# USB.net
KiCad netlist of a schematic drawn in Altium Designer
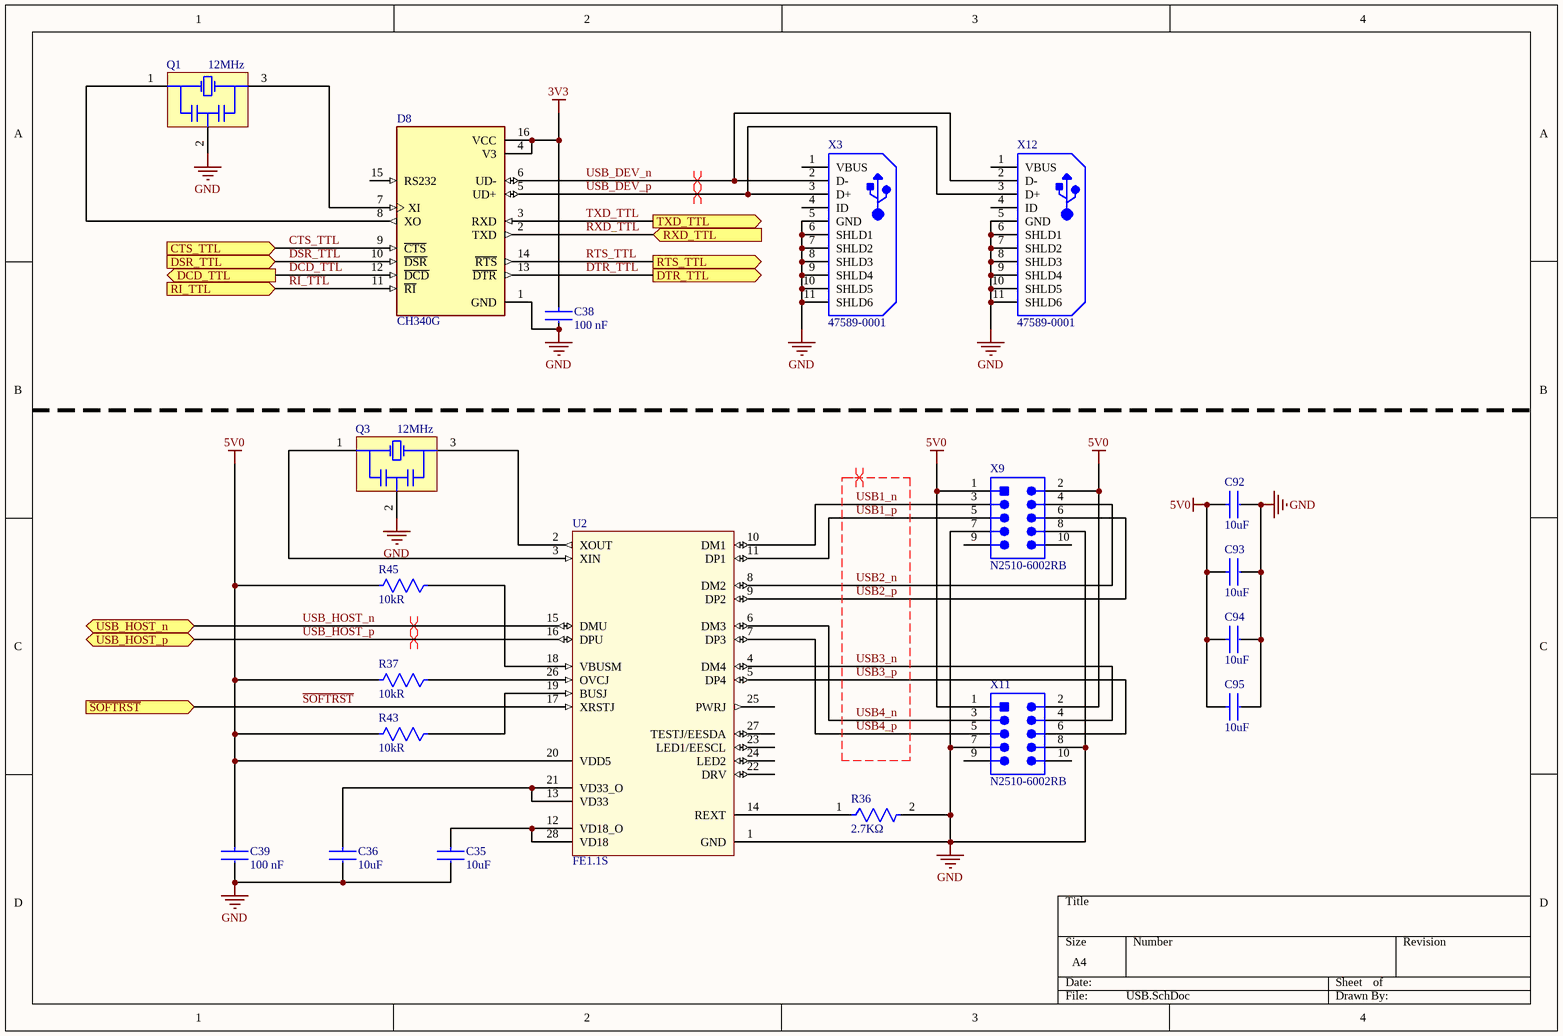
[diagram p0: USB.SchDoc]

(export (version "E")
  (design (tool "Eeschema 10.0.6"))
  (components
    (comp (ref "C35")
      (value "C0805C106K8PACTU")
      (footprint "FP-C0805C-DG-IPC_A")
      (description "CAP CER 10UF 10V X5R 0805")
      (fields (field (name "MANUFACTURER") "KEMET") (field (name "CAPACITANCE") "10uF"))
      (libsource (lib "zxevo") (part "CMP-2007-03243-2"))
    )
    (comp (ref "C36")
      (value "C0805C106K8PACTU")
      (footprint "FP-C0805C-DG-IPC_A")
      (description "CAP CER 10UF 10V X5R 0805")
      (fields (field (name "MANUFACTURER") "KEMET") (field (name "CAPACITANCE") "10uF"))
      (libsource (lib "zxevo") (part "CMP-2007-03243-2"))
    )
    (comp (ref "C38")
      (value "CC0805KRX7R9BB104")
      (footprint "FP-CC0805-0_85-IPC_A")
      (description "CAP CER 0.1UF 50V X7R 0805")
      (fields (field (name "MANUFACTURER") "Yageo") (field (name "CAPACITANCE") "100 nF"))
      (libsource (lib "zxevo") (part "CMP-2100-03606-3"))
    )
    (comp (ref "C39")
      (value "CC0805KRX7R9BB104")
      (footprint "FP-CC0805-0_85-IPC_A")
      (description "CAP CER 0.1UF 50V X7R 0805")
      (fields (field (name "MANUFACTURER") "Yageo") (field (name "CAPACITANCE") "100 nF"))
      (libsource (lib "zxevo") (part "CMP-2100-03606-3"))
    )
    (comp (ref "C92")
      (value "C0805C106K8PACTU")
      (footprint "FP-C0805C-DG-IPC_A")
      (description "CAP CER 10UF 10V X5R 0805")
      (fields (field (name "MANUFACTURER") "KEMET") (field (name "CAPACITANCE") "10uF"))
      (libsource (lib "zxevo") (part "CMP-2007-03243-2"))
    )
    (comp (ref "C93")
      (value "C0805C106K8PACTU")
      (footprint "FP-C0805C-DG-IPC_A")
      (description "CAP CER 10UF 10V X5R 0805")
      (fields (field (name "MANUFACTURER") "KEMET") (field (name "CAPACITANCE") "10uF"))
      (libsource (lib "zxevo") (part "CMP-2007-03243-2"))
    )
    (comp (ref "C94")
      (value "C0805C106K8PACTU")
      (footprint "FP-C0805C-DG-IPC_A")
      (description "CAP CER 10UF 10V X5R 0805")
      (fields (field (name "MANUFACTURER") "KEMET") (field (name "CAPACITANCE") "10uF"))
      (libsource (lib "zxevo") (part "CMP-2007-03243-2"))
    )
    (comp (ref "C95")
      (value "C0805C106K8PACTU")
      (footprint "FP-C0805C-DG-IPC_A")
      (description "CAP CER 10UF 10V X5R 0805")
      (fields (field (name "MANUFACTURER") "KEMET") (field (name "CAPACITANCE") "10uF"))
      (libsource (lib "zxevo") (part "CMP-2007-03243-2"))
    )
    (comp (ref "D8")
      (value "CH340G")
      (footprint "SOIC127P600X180-16N")
      (description "USB Interface Integrated Circuit")
      (libsource (lib "zxevo") (part "CH340G"))
    )
    (comp (ref "Q1")
      (value "CSTCE12M0G55Z-R0")
      (footprint "MURA-CSTCE_G_V")
      (description "Ceramic Resonator, 12 MHz, +/- 0.5%, -40 to 125 degC, 3-Pin SMD, RoHS, Tape and Reel")
      (fields (field (name "FREQUENCY") "12MHz") (field (name "MANUFACTURER") "Murata"))
      (libsource (lib "zxevo") (part "CMP-2000-06123-1"))
    )
    (comp (ref "Q3")
      (value "CSTCE12M0G55Z-R0")
      (footprint "MURA-CSTCE_G_V")
      (description "Ceramic Resonator, 12 MHz, +/- 0.5%, -40 to 125 degC, 3-Pin SMD, RoHS, Tape and Reel")
      (fields (field (name "FREQUENCY") "12MHz") (field (name "MANUFACTURER") "Murata"))
      (libsource (lib "zxevo") (part "CMP-2000-06123-1"))
    )
    (comp (ref "R36")
      (value "AC0805FR-072K7L")
      (footprint "FP-AC0805-IPC_A")
      (description "RES SMD 2.7K OHM 1% 1/8W 0805")
      (fields (field (name "RESISTANCE") "2.7KΩ") (field (name "MANUFACTURER") "Yageo"))
      (libsource (lib "zxevo") (part "CMP-2001-04496-2"))
    )
    (comp (ref "R37")
      (value "CR0805-JW-103ELF")
      (footprint "FP-CR0805-IPC_A")
      (description "Thick Film Chip Resistors 0805 10kΩ 0.125W 5% 200ppm/°C")
      (fields (field (name "RESISTANCE") "10kR") (field (name "MANUFACTURER") "Bourns"))
      (libsource (lib "zxevo") (part "CMP-07231-003873-1"))
    )
    (comp (ref "R43")
      (value "CR0805-JW-103ELF")
      (footprint "FP-CR0805-IPC_A")
      (description "Thick Film Chip Resistors 0805 10kΩ 0.125W 5% 200ppm/°C")
      (fields (field (name "RESISTANCE") "10kR") (field (name "MANUFACTURER") "Bourns"))
      (libsource (lib "zxevo") (part "CMP-07231-003873-1"))
    )
    (comp (ref "R45")
      (value "CR0805-JW-103ELF")
      (footprint "FP-CR0805-IPC_A")
      (description "Thick Film Chip Resistors 0805 10kΩ 0.125W 5% 200ppm/°C")
      (fields (field (name "RESISTANCE") "10kR") (field (name "MANUFACTURER") "Bourns"))
      (libsource (lib "zxevo") (part "CMP-07231-003873-1"))
    )
    (comp (ref "U2")
      (value "FE1.1S")
      (footprint "TSOP64P600X160-28L")
      (description "USB 2.0 HIGH SPEED 4-PORT HUB CONTROLLER")
      (fields (field (name "MANUFACTURER") "Terminus Technology Inc"))
      (libsource (lib "zxevo") (part "FE1.1S"))
    )
    (comp (ref "X3")
      (value "47589-0001")
      (footprint "MOLX-47589-0001_V")
      (description "Right Angle Female Type AB Micro USB Connector, 30 V, 1.8 A, -30 to 85 degC, RoHS, Tape and Reel")
      (fields (field (name "MANUFACTURER") "Molex"))
      (libsource (lib "zxevo") (part "CMP-2000-05610-1"))
    )
    (comp (ref "X9")
      (value "N2510-6002RB")
      (footprint "3M-N2510-6002-10_V")
      (fields (field (name "PARTNUMBER") "N2510") (field (name "MANUFACTURER") "3M"))
      (libsource (lib "zxevo") (part "CMP-2000-06794-1"))
    )
    (comp (ref "X11")
      (value "N2510-6002RB")
      (footprint "3M-N2510-6002-10_V")
      (fields (field (name "PARTNUMBER") "N2510") (field (name "MANUFACTURER") "3M"))
      (libsource (lib "zxevo") (part "CMP-2000-06794-1"))
    )
    (comp (ref "X12")
      (value "47589-0001")
      (footprint "MOLX-47589-0001_V")
      (description "Right Angle Female Type AB Micro USB Connector, 30 V, 1.8 A, -30 to 85 degC, RoHS, Tape and Reel")
      (fields (field (name "MANUFACTURER") "Molex"))
      (libsource (lib "zxevo") (part "CMP-2000-05610-1"))
    )
  )
  (nets
    (net (code "1") (name "/CTS_TTL") (class "Default")
      (node (ref "D8") (pin "9") (pinfunction "~{CTS}_9") (pintype "input"))
    )
    (net (code "2") (name "/DCD_TTL") (class "Default")
      (node (ref "D8") (pin "12") (pinfunction "~{DCD}_12") (pintype "input"))
    )
    (net (code "3") (name "/DSR_TTL") (class "Default")
      (node (ref "D8") (pin "10") (pinfunction "~{DSR}_10") (pintype "input"))
    )
    (net (code "4") (name "/DTR_TTL") (class "Default")
      (node (ref "D8") (pin "13") (pinfunction "~{DTR}_13") (pintype "output"))
    )
    (net (code "5") (name "/RI_TTL") (class "Default")
      (node (ref "D8") (pin "11") (pinfunction "~{RI}_11") (pintype "input"))
    )
    (net (code "6") (name "/RTS_TTL") (class "Default")
      (node (ref "D8") (pin "14") (pinfunction "~{RTS}_14") (pintype "output"))
    )
    (net (code "7") (name "/RXD_TTL") (class "Default")
      (node (ref "D8") (pin "2") (pinfunction "TXD_2") (pintype "output"))
    )
    (net (code "8") (name "/TXD_TTL") (class "Default")
      (node (ref "D8") (pin "3") (pinfunction "RXD_3") (pintype "input"))
    )
    (net (code "9") (name "/USB1_n") (class "Default")
      (node (ref "U2") (pin "10") (pinfunction "DM1_10") (pintype "bidirectional"))
      (node (ref "X9") (pin "3") (pinfunction "3_3") (pintype "passive"))
    )
    (net (code "10") (name "/USB1_p") (class "Default")
      (node (ref "U2") (pin "11") (pinfunction "DP1_11") (pintype "bidirectional"))
      (node (ref "X9") (pin "5") (pinfunction "5_5") (pintype "passive"))
    )
    (net (code "11") (name "/USB2_n") (class "Default")
      (node (ref "U2") (pin "8") (pinfunction "DM2_8") (pintype "bidirectional"))
      (node (ref "X9") (pin "4") (pinfunction "4_4") (pintype "passive"))
    )
    (net (code "12") (name "/USB2_p") (class "Default")
      (node (ref "U2") (pin "9") (pinfunction "DP2_9") (pintype "bidirectional"))
      (node (ref "X9") (pin "6") (pinfunction "6_6") (pintype "passive"))
    )
    (net (code "13") (name "/USB3_n") (class "Default")
      (node (ref "U2") (pin "4") (pinfunction "DM4_4") (pintype "bidirectional"))
      (node (ref "X11") (pin "4") (pinfunction "4_4") (pintype "passive"))
    )
    (net (code "14") (name "/USB3_p") (class "Default")
      (node (ref "U2") (pin "5") (pinfunction "DP4_5") (pintype "bidirectional"))
      (node (ref "X11") (pin "6") (pinfunction "6_6") (pintype "passive"))
    )
    (net (code "15") (name "/USB4_n") (class "Default")
      (node (ref "U2") (pin "6") (pinfunction "DM3_6") (pintype "bidirectional"))
      (node (ref "X11") (pin "3") (pinfunction "3_3") (pintype "passive"))
    )
    (net (code "16") (name "/USB4_p") (class "Default")
      (node (ref "U2") (pin "7") (pinfunction "DP3_7") (pintype "bidirectional"))
      (node (ref "X11") (pin "5") (pinfunction "5_5") (pintype "passive"))
    )
    (net (code "17") (name "/USB_DEV_n") (class "Default")
      (node (ref "D8") (pin "6") (pinfunction "UD-_6") (pintype "bidirectional"))
      (node (ref "X12") (pin "2") (pinfunction "D-_2") (pintype "passive"))
      (node (ref "X3") (pin "2") (pinfunction "D-_2") (pintype "passive"))
    )
    (net (code "18") (name "/USB_DEV_p") (class "Default")
      (node (ref "D8") (pin "5") (pinfunction "UD+_5") (pintype "bidirectional"))
      (node (ref "X12") (pin "3") (pinfunction "D+_3") (pintype "passive"))
      (node (ref "X3") (pin "3") (pinfunction "D+_3") (pintype "passive"))
    )
    (net (code "19") (name "/USB_HOST_n") (class "Default")
      (node (ref "U2") (pin "15") (pinfunction "DMU_15") (pintype "bidirectional"))
    )
    (net (code "20") (name "/USB_HOST_p") (class "Default")
      (node (ref "U2") (pin "16") (pinfunction "DPU_16") (pintype "bidirectional"))
    )
    (net (code "21") (name "/~{SOFTRST}") (class "Default")
      (node (ref "U2") (pin "17") (pinfunction "XRSTJ_17") (pintype "input"))
    )
    (net (code "22") (name "3V3") (class "Default")
      (node (ref "C38") (pin "1") (pinfunction "1_1") (pintype "passive"))
      (node (ref "D8") (pin "16") (pinfunction "VCC_16") (pintype "power_in"))
      (node (ref "D8") (pin "4") (pinfunction "V3_4") (pintype "power_in"))
    )
    (net (code "23") (name "5V0") (class "Default")
      (node (ref "C39") (pin "1") (pinfunction "1_1") (pintype "passive"))
      (node (ref "C92") (pin "1") (pinfunction "1_1") (pintype "passive"))
      (node (ref "C93") (pin "1") (pinfunction "1_1") (pintype "passive"))
      (node (ref "C94") (pin "1") (pinfunction "1_1") (pintype "passive"))
      (node (ref "C95") (pin "1") (pinfunction "1_1") (pintype "passive"))
      (node (ref "R37") (pin "2") (pinfunction "2_2") (pintype "passive"))
      (node (ref "R43") (pin "2") (pinfunction "2_2") (pintype "passive"))
      (node (ref "R45") (pin "2") (pinfunction "2_2") (pintype "passive"))
      (node (ref "U2") (pin "20") (pinfunction "VDD5_20") (pintype "power_in"))
      (node (ref "X11") (pin "1") (pinfunction "1_1") (pintype "passive"))
      (node (ref "X11") (pin "2") (pinfunction "2_2") (pintype "passive"))
      (node (ref "X9") (pin "1") (pinfunction "1_1") (pintype "passive"))
      (node (ref "X9") (pin "2") (pinfunction "2_2") (pintype "passive"))
    )
    (net (code "24") (name "GND") (class "Default")
      (node (ref "C35") (pin "2") (pinfunction "2_2") (pintype "passive"))
      (node (ref "C36") (pin "2") (pinfunction "2_2") (pintype "passive"))
      (node (ref "C38") (pin "2") (pinfunction "2_2") (pintype "passive"))
      (node (ref "C39") (pin "2") (pinfunction "2_2") (pintype "passive"))
      (node (ref "C92") (pin "2") (pinfunction "2_2") (pintype "passive"))
      (node (ref "C93") (pin "2") (pinfunction "2_2") (pintype "passive"))
      (node (ref "C94") (pin "2") (pinfunction "2_2") (pintype "passive"))
      (node (ref "C95") (pin "2") (pinfunction "2_2") (pintype "passive"))
      (node (ref "D8") (pin "1") (pinfunction "GND_1") (pintype "power_in"))
      (node (ref "Q1") (pin "2") (pinfunction "GND_2") (pintype "power_in"))
      (node (ref "Q3") (pin "2") (pinfunction "GND_2") (pintype "power_in"))
      (node (ref "R36") (pin "2") (pinfunction "2_2") (pintype "passive"))
      (node (ref "U2") (pin "1") (pinfunction "GND_1") (pintype "power_in"))
      (node (ref "X11") (pin "7") (pinfunction "7_7") (pintype "passive"))
      (node (ref "X11") (pin "8") (pinfunction "8_8") (pintype "passive"))
      (node (ref "X12") (pin "10") (pinfunction "SHLD5_10") (pintype "passive"))
      (node (ref "X12") (pin "11") (pinfunction "SHLD6_11") (pintype "passive"))
      (node (ref "X12") (pin "5") (pinfunction "GND_5") (pintype "passive"))
      (node (ref "X12") (pin "6") (pinfunction "SHLD1_6") (pintype "passive"))
      (node (ref "X12") (pin "7") (pinfunction "SHLD2_7") (pintype "passive"))
      (node (ref "X12") (pin "8") (pinfunction "SHLD3_8") (pintype "passive"))
      (node (ref "X12") (pin "9") (pinfunction "SHLD4_9") (pintype "passive"))
      (node (ref "X3") (pin "10") (pinfunction "SHLD5_10") (pintype "passive"))
      (node (ref "X3") (pin "11") (pinfunction "SHLD6_11") (pintype "passive"))
      (node (ref "X3") (pin "5") (pinfunction "GND_5") (pintype "passive"))
      (node (ref "X3") (pin "6") (pinfunction "SHLD1_6") (pintype "passive"))
      (node (ref "X3") (pin "7") (pinfunction "SHLD2_7") (pintype "passive"))
      (node (ref "X3") (pin "8") (pinfunction "SHLD3_8") (pintype "passive"))
      (node (ref "X3") (pin "9") (pinfunction "SHLD4_9") (pintype "passive"))
      (node (ref "X9") (pin "7") (pinfunction "7_7") (pintype "passive"))
      (node (ref "X9") (pin "8") (pinfunction "8_8") (pintype "passive"))
    )
    (net (code "25") (name "Net-(D8-XI)") (class "Default")
      (node (ref "D8") (pin "7") (pinfunction "XI_7") (pintype "input"))
      (node (ref "Q1") (pin "3") (pinfunction "X2_3") (pintype "passive"))
    )
    (net (code "26") (name "Net-(D8-XO)") (class "Default")
      (node (ref "D8") (pin "8") (pinfunction "XO_8") (pintype "output"))
      (node (ref "Q1") (pin "1") (pinfunction "X1_1") (pintype "passive"))
    )
    (net (code "27") (name "Net-(Q3-X1)") (class "Default")
      (node (ref "Q3") (pin "1") (pinfunction "X1_1") (pintype "passive"))
      (node (ref "U2") (pin "3") (pinfunction "XIN_3") (pintype "input"))
    )
    (net (code "28") (name "Net-(Q3-X2)") (class "Default")
      (node (ref "Q3") (pin "3") (pinfunction "X2_3") (pintype "passive"))
      (node (ref "U2") (pin "2") (pinfunction "XOUT_2") (pintype "output"))
    )
    (net (code "29") (name "Net-(U2-BUSJ)") (class "Default")
      (node (ref "R43") (pin "1") (pinfunction "1_1") (pintype "passive"))
      (node (ref "U2") (pin "19") (pinfunction "BUSJ_19") (pintype "input"))
    )
    (net (code "30") (name "Net-(U2-OVCJ)") (class "Default")
      (node (ref "R37") (pin "1") (pinfunction "1_1") (pintype "passive"))
      (node (ref "U2") (pin "26") (pinfunction "OVCJ_26") (pintype "input"))
    )
    (net (code "31") (name "Net-(U2-REXT)") (class "Default")
      (node (ref "R36") (pin "1") (pinfunction "1_1") (pintype "passive"))
      (node (ref "U2") (pin "14") (pinfunction "REXT_14") (pintype "power_in"))
    )
    (net (code "32") (name "Net-(U2-VBUSM)") (class "Default")
      (node (ref "R45") (pin "1") (pinfunction "1_1") (pintype "passive"))
      (node (ref "U2") (pin "18") (pinfunction "VBUSM_18") (pintype "input"))
    )
    (net (code "33") (name "Net-(U2-VD18)") (class "Default")
      (node (ref "C35") (pin "1") (pinfunction "1_1") (pintype "passive"))
      (node (ref "U2") (pin "12") (pinfunction "VD18_O_12") (pintype "power_in"))
      (node (ref "U2") (pin "28") (pinfunction "VD18_28") (pintype "power_in"))
    )
    (net (code "34") (name "Net-(U2-VD33)") (class "Default")
      (node (ref "C36") (pin "1") (pinfunction "1_1") (pintype "passive"))
      (node (ref "U2") (pin "13") (pinfunction "VD33_13") (pintype "power_in"))
      (node (ref "U2") (pin "21") (pinfunction "VD33_O_21") (pintype "power_in"))
    )
    (net (code "35") (name "unconnected-(D8-RS232-Pad15)") (class "Default")
      (node (ref "D8") (pin "15") (pinfunction "RS232_15") (pintype "input"))
    )
    (net (code "36") (name "unconnected-(U2-DRV-Pad22)") (class "Default")
      (node (ref "U2") (pin "22") (pinfunction "DRV_22") (pintype "bidirectional"))
    )
    (net (code "37") (name "unconnected-(U2-LED1{slash}EESCL-Pad23)") (class "Default")
      (node (ref "U2") (pin "23") (pinfunction "LED1/EESCL_23") (pintype "bidirectional"))
    )
    (net (code "38") (name "unconnected-(U2-LED2-Pad24)") (class "Default")
      (node (ref "U2") (pin "24") (pinfunction "LED2_24") (pintype "bidirectional"))
    )
    (net (code "39") (name "unconnected-(U2-PWRJ-Pad25)") (class "Default")
      (node (ref "U2") (pin "25") (pinfunction "PWRJ_25") (pintype "output"))
    )
    (net (code "40") (name "unconnected-(U2-TESTJ{slash}EESDA-Pad27)") (class "Default")
      (node (ref "U2") (pin "27") (pinfunction "TESTJ/EESDA_27") (pintype "bidirectional"))
    )
    (net (code "41") (name "unconnected-(X3-ID-Pad4)") (class "Default")
      (node (ref "X3") (pin "4") (pinfunction "ID_4") (pintype "passive"))
    )
    (net (code "42") (name "unconnected-(X3-VBUS-Pad1)") (class "Default")
      (node (ref "X3") (pin "1") (pinfunction "VBUS_1") (pintype "passive"))
    )
    (net (code "43") (name "unconnected-(X9-Pad9)") (class "Default")
      (node (ref "X9") (pin "9") (pinfunction "9_9") (pintype "passive"))
    )
    (net (code "44") (name "unconnected-(X9-Pad10)") (class "Default")
      (node (ref "X9") (pin "10") (pinfunction "10_10") (pintype "passive"))
    )
    (net (code "45") (name "unconnected-(X11-Pad9)") (class "Default")
      (node (ref "X11") (pin "9") (pinfunction "9_9") (pintype "passive"))
    )
    (net (code "46") (name "unconnected-(X11-Pad10)") (class "Default")
      (node (ref "X11") (pin "10") (pinfunction "10_10") (pintype "passive"))
    )
    (net (code "47") (name "unconnected-(X12-ID-Pad4)") (class "Default")
      (node (ref "X12") (pin "4") (pinfunction "ID_4") (pintype "passive"))
    )
    (net (code "48") (name "unconnected-(X12-VBUS-Pad1)") (class "Default")
      (node (ref "X12") (pin "1") (pinfunction "VBUS_1") (pintype "passive"))
    )
  )
)
